# ESP32.net
KiCad netlist of a schematic drawn in EasyEDA
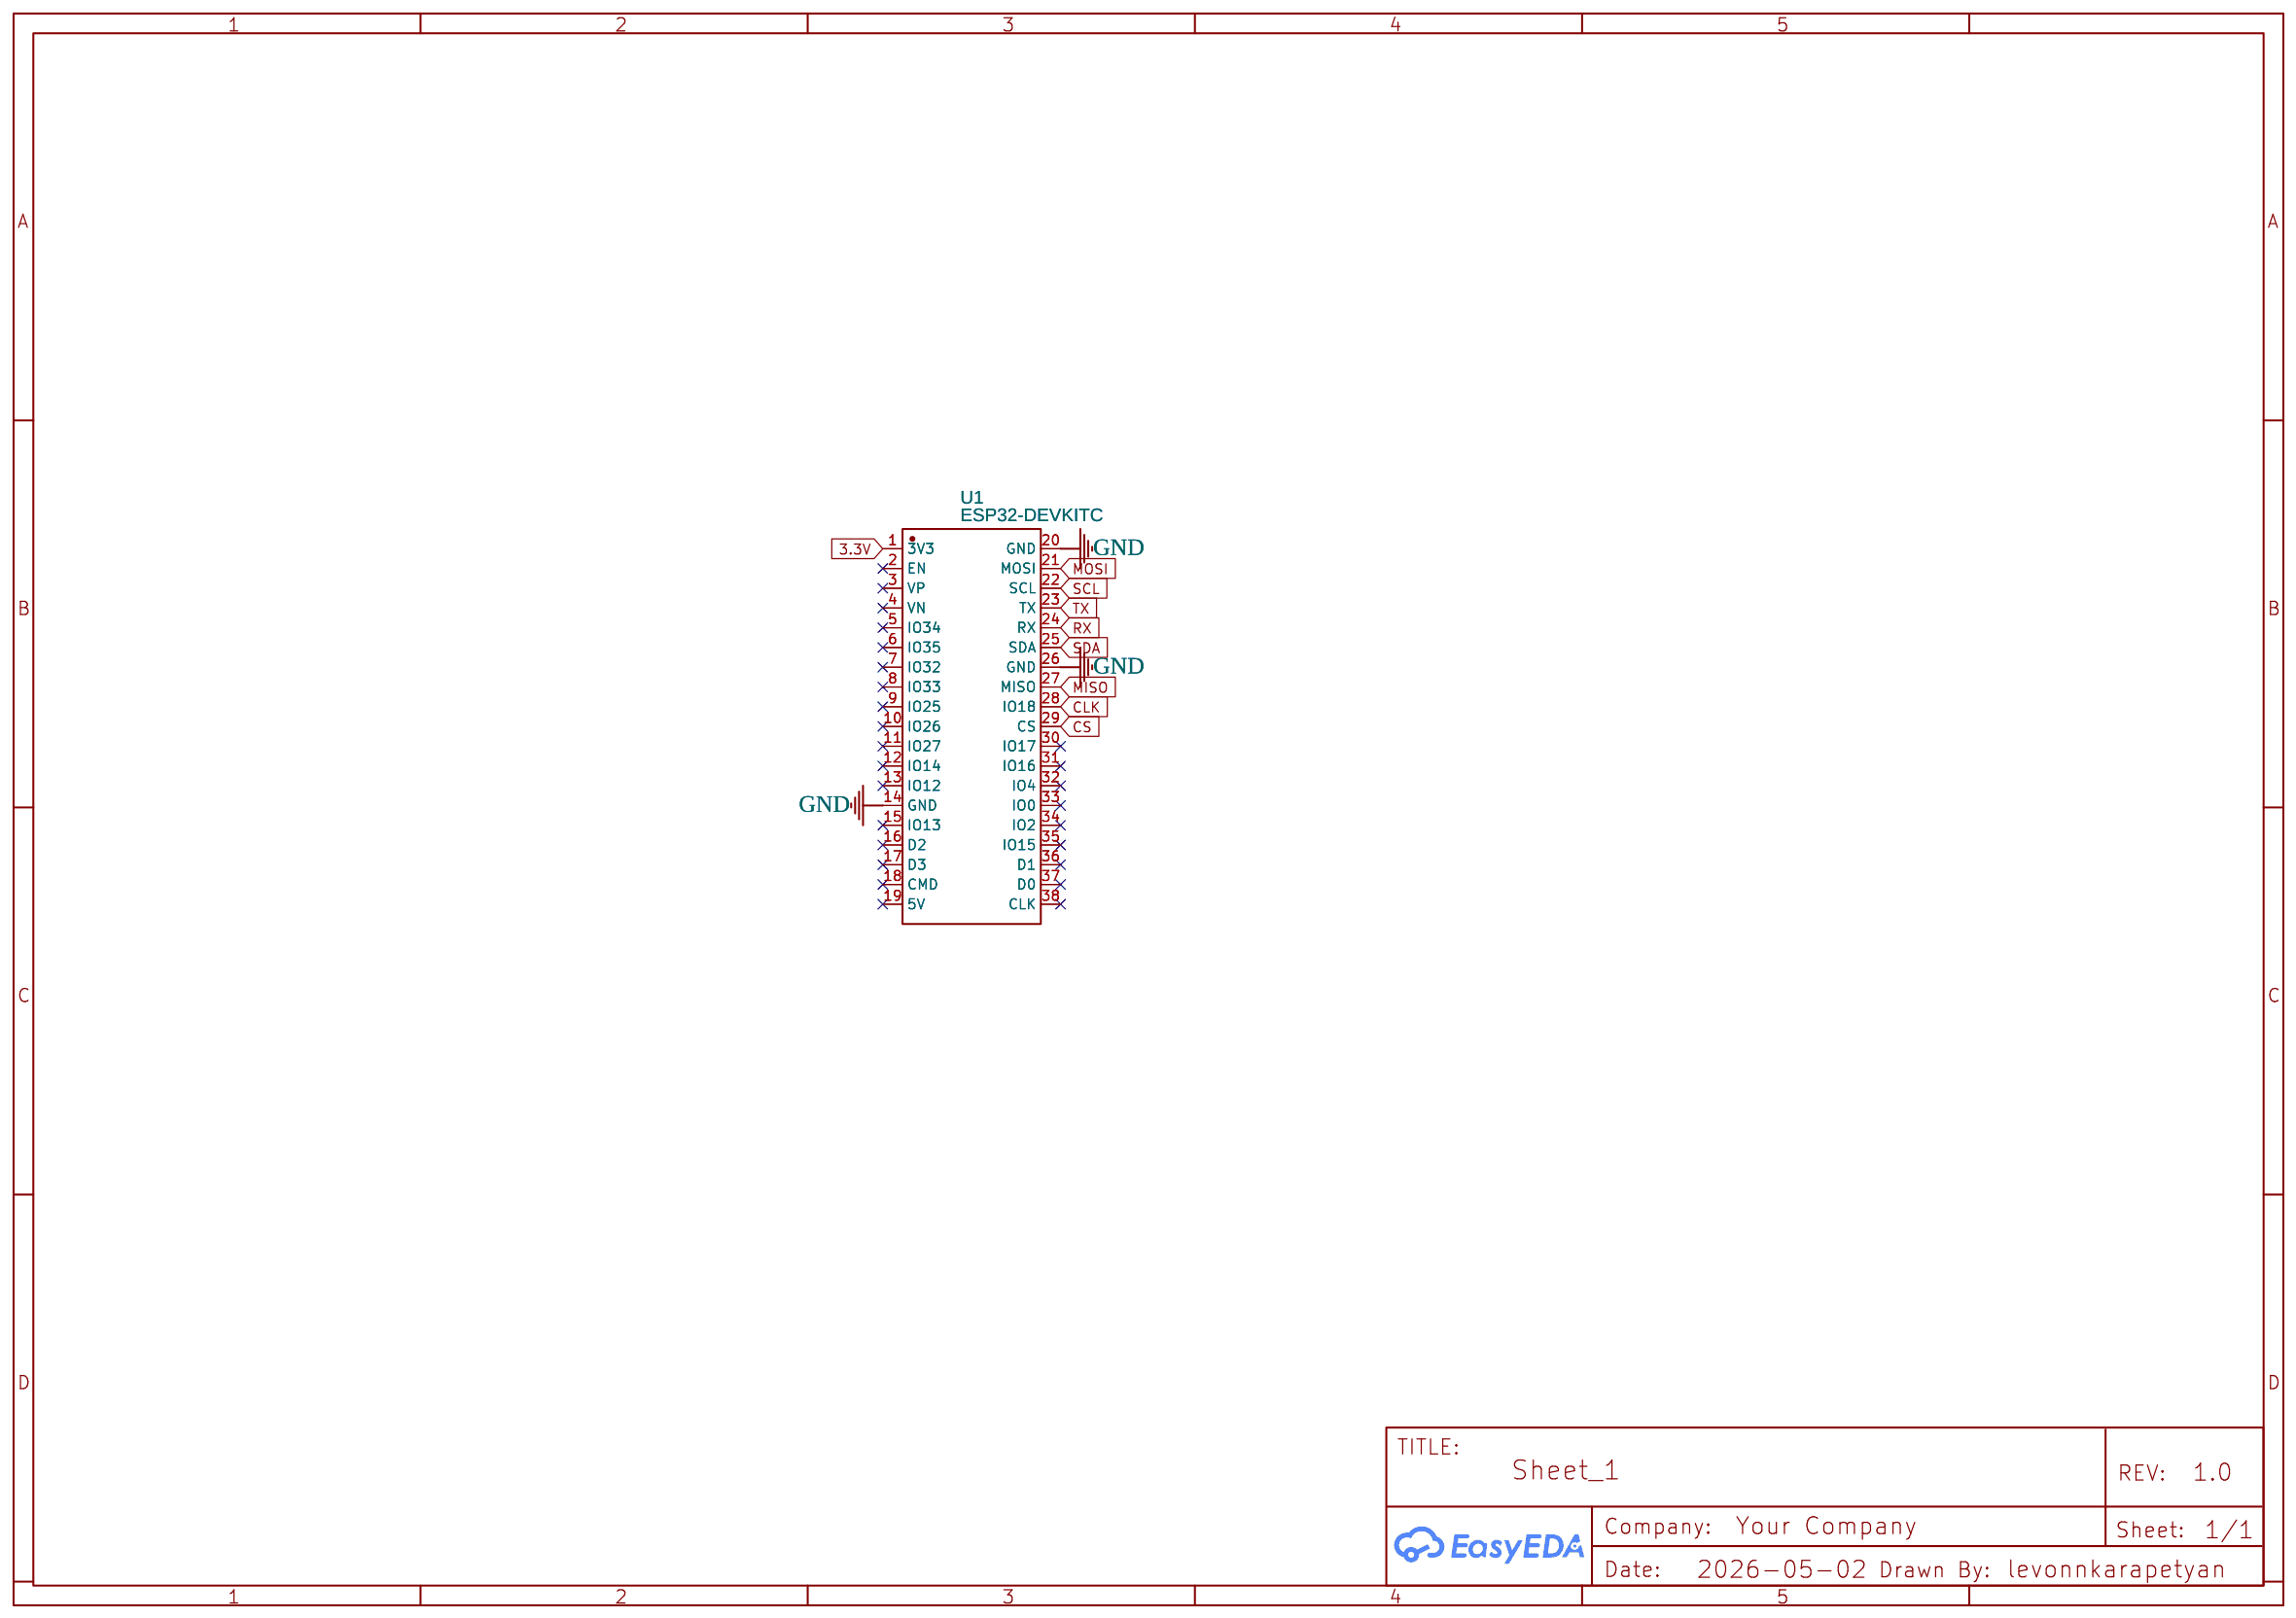
[diagram p0: schematic sheet]

(export (version "E")
  (design (tool "Eeschema 10.0.6"))
  (components
    (comp (ref "U1")
      (value "ESP32-DEVKITC")
      (fields
        (field (name "Manufacturer Part") "ESP32-DevKitC")
        (field (name "Manufacturer") "ESPRESSIF(乐鑫)")
      )
      (libsource (lib "") (part "ESP32-DEVKITC"))
    )
  )
  (nets
    (net (code "1") (name "3.3V") (class "Default")
      (node (ref "U1") (pin "1") (pinfunction "3V3_1") (pintype "unspecified"))
    )
    (net (code "2") (name "CLK") (class "Default")
      (node (ref "U1") (pin "28") (pinfunction "IO18_28") (pintype "unspecified"))
    )
    (net (code "3") (name "CS") (class "Default")
      (node (ref "U1") (pin "29") (pinfunction "CS_29") (pintype "unspecified"))
    )
    (net (code "4") (name "GND") (class "Default")
      (node (ref "U1") (pin "14") (pinfunction "GND_14") (pintype "unspecified"))
      (node (ref "U1") (pin "20") (pinfunction "GND_20") (pintype "unspecified"))
      (node (ref "U1") (pin "26") (pinfunction "GND_26") (pintype "unspecified"))
    )
    (net (code "5") (name "MISO") (class "Default")
      (node (ref "U1") (pin "27") (pinfunction "MISO_27") (pintype "unspecified"))
    )
    (net (code "6") (name "MOSI") (class "Default")
      (node (ref "U1") (pin "21") (pinfunction "MOSI_21") (pintype "unspecified"))
    )
    (net (code "7") (name "RX") (class "Default")
      (node (ref "U1") (pin "24") (pinfunction "RX_24") (pintype "unspecified"))
    )
    (net (code "8") (name "SCL") (class "Default")
      (node (ref "U1") (pin "22") (pinfunction "SCL_22") (pintype "unspecified"))
    )
    (net (code "9") (name "SDA") (class "Default")
      (node (ref "U1") (pin "25") (pinfunction "SDA_25") (pintype "unspecified"))
    )
    (net (code "10") (name "TX") (class "Default")
      (node (ref "U1") (pin "23") (pinfunction "TX_23") (pintype "unspecified"))
    )
    (net (code "11") (name "unconnected-(U1-5V-Pad19)") (class "Default")
      (node (ref "U1") (pin "19") (pinfunction "5V_19") (pintype "unspecified+no_connect"))
    )
    (net (code "12") (name "unconnected-(U1-CLK-Pad38)") (class "Default")
      (node (ref "U1") (pin "38") (pinfunction "CLK_38") (pintype "unspecified+no_connect"))
    )
    (net (code "13") (name "unconnected-(U1-CMD-Pad18)") (class "Default")
      (node (ref "U1") (pin "18") (pinfunction "CMD_18") (pintype "unspecified+no_connect"))
    )
    (net (code "14") (name "unconnected-(U1-D0-Pad37)") (class "Default")
      (node (ref "U1") (pin "37") (pinfunction "D0_37") (pintype "unspecified+no_connect"))
    )
    (net (code "15") (name "unconnected-(U1-D1-Pad36)") (class "Default")
      (node (ref "U1") (pin "36") (pinfunction "D1_36") (pintype "unspecified+no_connect"))
    )
    (net (code "16") (name "unconnected-(U1-D2-Pad16)") (class "Default")
      (node (ref "U1") (pin "16") (pinfunction "D2_16") (pintype "unspecified+no_connect"))
    )
    (net (code "17") (name "unconnected-(U1-D3-Pad17)") (class "Default")
      (node (ref "U1") (pin "17") (pinfunction "D3_17") (pintype "unspecified+no_connect"))
    )
    (net (code "18") (name "unconnected-(U1-EN-Pad2)") (class "Default")
      (node (ref "U1") (pin "2") (pinfunction "EN_2") (pintype "unspecified+no_connect"))
    )
    (net (code "19") (name "unconnected-(U1-IO0-Pad33)") (class "Default")
      (node (ref "U1") (pin "33") (pinfunction "IO0_33") (pintype "unspecified+no_connect"))
    )
    (net (code "20") (name "unconnected-(U1-IO2-Pad34)") (class "Default")
      (node (ref "U1") (pin "34") (pinfunction "IO2_34") (pintype "unspecified+no_connect"))
    )
    (net (code "21") (name "unconnected-(U1-IO4-Pad32)") (class "Default")
      (node (ref "U1") (pin "32") (pinfunction "IO4_32") (pintype "unspecified+no_connect"))
    )
    (net (code "22") (name "unconnected-(U1-IO12-Pad13)") (class "Default")
      (node (ref "U1") (pin "13") (pinfunction "IO12_13") (pintype "unspecified+no_connect"))
    )
    (net (code "23") (name "unconnected-(U1-IO13-Pad15)") (class "Default")
      (node (ref "U1") (pin "15") (pinfunction "IO13_15") (pintype "unspecified+no_connect"))
    )
    (net (code "24") (name "unconnected-(U1-IO14-Pad12)") (class "Default")
      (node (ref "U1") (pin "12") (pinfunction "IO14_12") (pintype "unspecified+no_connect"))
    )
    (net (code "25") (name "unconnected-(U1-IO15-Pad35)") (class "Default")
      (node (ref "U1") (pin "35") (pinfunction "IO15_35") (pintype "unspecified+no_connect"))
    )
    (net (code "26") (name "unconnected-(U1-IO16-Pad31)") (class "Default")
      (node (ref "U1") (pin "31") (pinfunction "IO16_31") (pintype "unspecified+no_connect"))
    )
    (net (code "27") (name "unconnected-(U1-IO17-Pad30)") (class "Default")
      (node (ref "U1") (pin "30") (pinfunction "IO17_30") (pintype "unspecified+no_connect"))
    )
    (net (code "28") (name "unconnected-(U1-IO25-Pad9)") (class "Default")
      (node (ref "U1") (pin "9") (pinfunction "IO25_9") (pintype "unspecified+no_connect"))
    )
    (net (code "29") (name "unconnected-(U1-IO26-Pad10)") (class "Default")
      (node (ref "U1") (pin "10") (pinfunction "IO26_10") (pintype "unspecified+no_connect"))
    )
    (net (code "30") (name "unconnected-(U1-IO27-Pad11)") (class "Default")
      (node (ref "U1") (pin "11") (pinfunction "IO27_11") (pintype "unspecified+no_connect"))
    )
    (net (code "31") (name "unconnected-(U1-IO32-Pad7)") (class "Default")
      (node (ref "U1") (pin "7") (pinfunction "IO32_7") (pintype "unspecified+no_connect"))
    )
    (net (code "32") (name "unconnected-(U1-IO33-Pad8)") (class "Default")
      (node (ref "U1") (pin "8") (pinfunction "IO33_8") (pintype "unspecified+no_connect"))
    )
    (net (code "33") (name "unconnected-(U1-IO34-Pad5)") (class "Default")
      (node (ref "U1") (pin "5") (pinfunction "IO34_5") (pintype "unspecified+no_connect"))
    )
    (net (code "34") (name "unconnected-(U1-IO35-Pad6)") (class "Default")
      (node (ref "U1") (pin "6") (pinfunction "IO35_6") (pintype "unspecified+no_connect"))
    )
    (net (code "35") (name "unconnected-(U1-VN-Pad4)") (class "Default")
      (node (ref "U1") (pin "4") (pinfunction "VN_4") (pintype "unspecified+no_connect"))
    )
    (net (code "36") (name "unconnected-(U1-VP-Pad3)") (class "Default")
      (node (ref "U1") (pin "3") (pinfunction "VP_3") (pintype "unspecified+no_connect"))
    )
  )
)
